# 4-Port_USB_HUB_SCH.net
KiCad netlist of a schematic drawn in Altium Designer
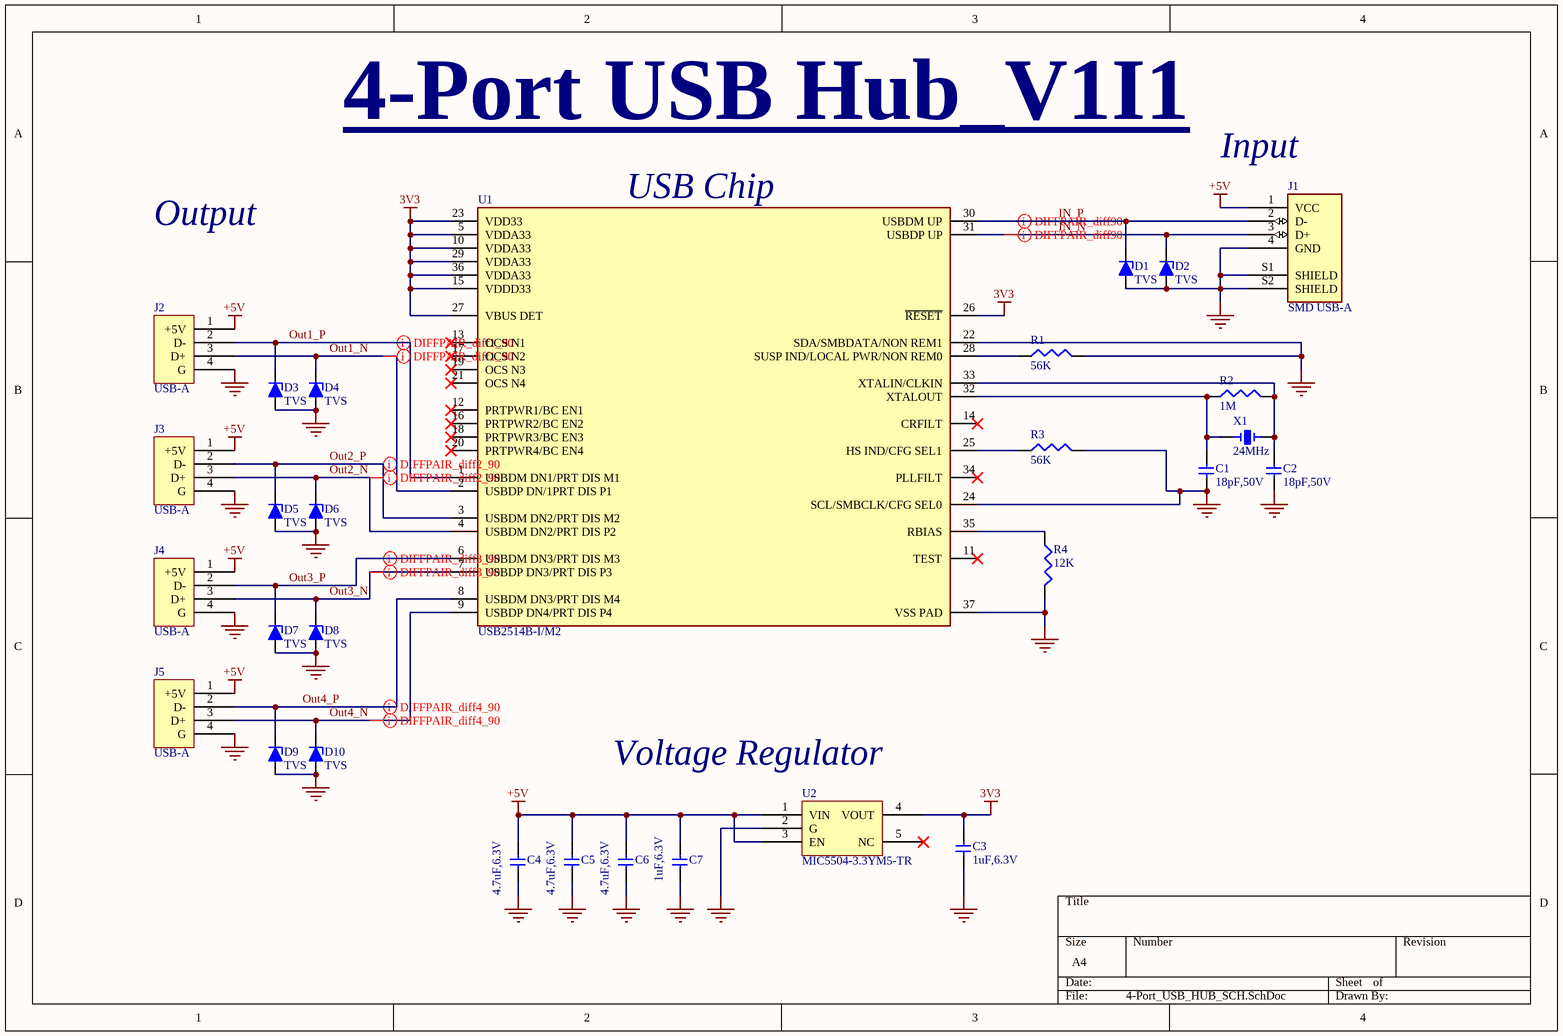
[diagram p0: 4-Port_USB_HUB_SCH.SchDoc]

(export (version "E")
  (design (tool "Eeschema 10.0.6"))
  (components
    (comp (ref "C1")
      (value "18pF,50V")
      (footprint "18pF")
      (description "18PF 50V 0805")
      (fields
        (field (name "MANUFACTURER") "KEMET")
        (field (name "MANUFACTURER PART NUMBER") "C0805C180J5GACTU")
      )
      (libsource (lib "4-Port_USB_HUB_SCHLib") (part "C0805C180J5GACTU"))
    )
    (comp (ref "C2")
      (value "18pF,50V")
      (footprint "18pF")
      (description "18PF 50V 0805")
      (fields
        (field (name "MANUFACTURER") "KEMET")
        (field (name "MANUFACTURER PART NUMBER") "C0805C180J5GACTU")
      )
      (libsource (lib "4-Port_USB_HUB_SCHLib") (part "C0805C180J5GACTU"))
    )
    (comp (ref "C3")
      (value "1uF,6.3V")
      (footprint "1uF_CAP")
      (description "1uF 6.3V 0402")
      (fields
        (field (name "MANUFACTURER") "KEMET")
        (field (name "MANUFACTURER PART NUMBER") "C0402C105K9PACTU")
      )
      (libsource (lib "4-Port_USB_HUB_SCHLib") (part "C0402C105K9PACTU"))
    )
    (comp (ref "C4")
      (value "4.7uF,6.3V")
      (footprint "4.7uF_CAP")
      (description "4.7uF 6.3V 0402")
      (fields
        (field (name "MANUFACTURER") "Murata")
        (field (name "MANUFACTURER PART NUMBER") "GRM155R60J475ME47D")
      )
      (libsource (lib "4-Port_USB_HUB_SCHLib") (part "GRM155R60J475ME47D"))
    )
    (comp (ref "C5")
      (value "4.7uF,6.3V")
      (footprint "4.7uF_CAP")
      (description "4.7uF 6.3V 0402")
      (fields
        (field (name "MANUFACTURER") "Murata")
        (field (name "MANUFACTURER PART NUMBER") "GRM155R60J475ME47D")
      )
      (libsource (lib "4-Port_USB_HUB_SCHLib") (part "GRM155R60J475ME47D"))
    )
    (comp (ref "C6")
      (value "4.7uF,6.3V")
      (footprint "4.7uF_CAP")
      (description "4.7uF 6.3V 0402")
      (fields
        (field (name "MANUFACTURER") "Murata")
        (field (name "MANUFACTURER PART NUMBER") "GRM155R60J475ME47D")
      )
      (libsource (lib "4-Port_USB_HUB_SCHLib") (part "GRM155R60J475ME47D"))
    )
    (comp (ref "C7")
      (value "1uF,6.3V")
      (footprint "1uF_CAP")
      (description "1uF 6.3V 0402")
      (fields
        (field (name "MANUFACTURER") "KEMET")
        (field (name "MANUFACTURER PART NUMBER") "C0402C105K9PACTU")
      )
      (libsource (lib "4-Port_USB_HUB_SCHLib") (part "C0402C105K9PACTU"))
    )
    (comp (ref "D1")
      (value "TVS")
      (footprint "ESD Diode")
      (description "TVS Diode")
      (fields
        (field (name "MANUFACTURER") "ON Semiconductor")
        (field (name "MANUFACTURER PART NUMBER") "ESD9B3.3ST5G")
      )
      (libsource (lib "4-Port_USB_HUB_SCHLib") (part "ESD9B3.3ST5G"))
    )
    (comp (ref "D2")
      (value "TVS")
      (footprint "ESD Diode")
      (description "TVS Diode")
      (fields
        (field (name "MANUFACTURER") "ON Semiconductor")
        (field (name "MANUFACTURER PART NUMBER") "ESD9B3.3ST5G")
      )
      (libsource (lib "4-Port_USB_HUB_SCHLib") (part "ESD9B3.3ST5G"))
    )
    (comp (ref "D3")
      (value "TVS")
      (footprint "ESD Diode")
      (description "TVS Diode")
      (fields
        (field (name "MANUFACTURER") "ON Semiconductor")
        (field (name "MANUFACTURER PART NUMBER") "ESD9B3.3ST5G")
      )
      (libsource (lib "4-Port_USB_HUB_SCHLib") (part "ESD9B3.3ST5G"))
    )
    (comp (ref "D4")
      (value "TVS")
      (footprint "ESD Diode")
      (description "TVS Diode")
      (fields
        (field (name "MANUFACTURER") "ON Semiconductor")
        (field (name "MANUFACTURER PART NUMBER") "ESD9B3.3ST5G")
      )
      (libsource (lib "4-Port_USB_HUB_SCHLib") (part "ESD9B3.3ST5G"))
    )
    (comp (ref "D5")
      (value "TVS")
      (footprint "ESD Diode")
      (description "TVS Diode")
      (fields
        (field (name "MANUFACTURER") "ON Semiconductor")
        (field (name "MANUFACTURER PART NUMBER") "ESD9B3.3ST5G")
      )
      (libsource (lib "4-Port_USB_HUB_SCHLib") (part "ESD9B3.3ST5G"))
    )
    (comp (ref "D6")
      (value "TVS")
      (footprint "ESD Diode")
      (description "TVS Diode")
      (fields
        (field (name "MANUFACTURER") "ON Semiconductor")
        (field (name "MANUFACTURER PART NUMBER") "ESD9B3.3ST5G")
      )
      (libsource (lib "4-Port_USB_HUB_SCHLib") (part "ESD9B3.3ST5G"))
    )
    (comp (ref "D7")
      (value "TVS")
      (footprint "ESD Diode")
      (description "TVS Diode")
      (fields
        (field (name "MANUFACTURER") "ON Semiconductor")
        (field (name "MANUFACTURER PART NUMBER") "ESD9B3.3ST5G")
      )
      (libsource (lib "4-Port_USB_HUB_SCHLib") (part "ESD9B3.3ST5G"))
    )
    (comp (ref "D8")
      (value "TVS")
      (footprint "ESD Diode")
      (description "TVS Diode")
      (fields
        (field (name "MANUFACTURER") "ON Semiconductor")
        (field (name "MANUFACTURER PART NUMBER") "ESD9B3.3ST5G")
      )
      (libsource (lib "4-Port_USB_HUB_SCHLib") (part "ESD9B3.3ST5G"))
    )
    (comp (ref "D9")
      (value "TVS")
      (footprint "ESD Diode")
      (description "TVS Diode")
      (fields
        (field (name "MANUFACTURER") "ON Semiconductor")
        (field (name "MANUFACTURER PART NUMBER") "ESD9B3.3ST5G")
      )
      (libsource (lib "4-Port_USB_HUB_SCHLib") (part "ESD9B3.3ST5G"))
    )
    (comp (ref "D10")
      (value "TVS")
      (footprint "ESD Diode")
      (description "TVS Diode")
      (fields
        (field (name "MANUFACTURER") "ON Semiconductor")
        (field (name "MANUFACTURER PART NUMBER") "ESD9B3.3ST5G")
      )
      (libsource (lib "4-Port_USB_HUB_SCHLib") (part "ESD9B3.3ST5G"))
    )
    (comp (ref "J1")
      (value "SMD USB-A")
      (footprint "SMD USB-A")
      (description "USB - A USB 2.0 Receptacle Connector 4 Position Surface Mount, Right Angle, Horizontal")
      (fields
        (field (name "MANUFACTURER") "Samtec")
        (field (name "MANUFACTURER PART NUMBER") "USB-A-S-S-B-SM2")
      )
      (libsource (lib "4-Port_USB_HUB_SCHLib") (part "USB-A-S-S-B-SM2"))
    )
    (comp (ref "J2")
      (value "USB-A")
      (footprint "USB_Connector")
      (description "Conn USB SKT 4 POS Solder ST Thru-Hole 4 Terminal 1 Port")
      (fields
        (field (name "MANUFACTURER") "Kycon")
        (field (name "MANUFACTURER PART NUMBER") "KUSBVX-AS1N-B30")
      )
      (libsource (lib "4-Port_USB_HUB_SCHLib") (part "KUSBVX-AS1N-B30"))
    )
    (comp (ref "J3")
      (value "USB-A")
      (footprint "USB_Connector")
      (description "Conn USB SKT 4 POS Solder ST Thru-Hole 4 Terminal 1 Port")
      (fields
        (field (name "MANUFACTURER") "Kycon")
        (field (name "MANUFACTURER PART NUMBER") "KUSBVX-AS1N-B30")
      )
      (libsource (lib "4-Port_USB_HUB_SCHLib") (part "KUSBVX-AS1N-B30"))
    )
    (comp (ref "J4")
      (value "USB-A")
      (footprint "USB_Connector")
      (description "Conn USB SKT 4 POS Solder ST Thru-Hole 4 Terminal 1 Port")
      (fields
        (field (name "MANUFACTURER") "Kycon")
        (field (name "MANUFACTURER PART NUMBER") "KUSBVX-AS1N-B30")
      )
      (libsource (lib "4-Port_USB_HUB_SCHLib") (part "KUSBVX-AS1N-B30"))
    )
    (comp (ref "J5")
      (value "USB-A")
      (footprint "USB_Connector")
      (description "Conn USB SKT 4 POS Solder ST Thru-Hole 4 Terminal 1 Port")
      (fields
        (field (name "MANUFACTURER") "Kycon")
        (field (name "MANUFACTURER PART NUMBER") "KUSBVX-AS1N-B30")
      )
      (libsource (lib "4-Port_USB_HUB_SCHLib") (part "KUSBVX-AS1N-B30"))
    )
    (comp (ref "R1")
      (value "56K")
      (footprint "56K")
      (fields
        (field (name "MANUFACTURER") "Yageo")
        (field (name "MANUFACTURER PART NUMBER") "RC0402JR-0756KL")
        (field (name "TOLERANCE") "5%")
      )
      (libsource (lib "4-Port_USB_HUB_SCHLib") (part "RC0402JR-0756KL"))
    )
    (comp (ref "R2")
      (value "1M")
      (footprint "1M Res")
      (description "1M OHM")
      (fields
        (field (name "MANUFACTURER") "Yageo")
        (field (name "MANUFACTURER PART NUMBER") "RC0402FR-071ML")
      )
      (libsource (lib "4-Port_USB_HUB_SCHLib") (part "RC0402FR-071ML"))
    )
    (comp (ref "R3")
      (value "56K")
      (footprint "56K")
      (fields
        (field (name "MANUFACTURER") "Yageo")
        (field (name "MANUFACTURER PART NUMBER") "RC0402JR-0756KL")
        (field (name "TOLERANCE") "5%")
      )
      (libsource (lib "4-Port_USB_HUB_SCHLib") (part "RC0402JR-0756KL"))
    )
    (comp (ref "R4")
      (value "12K")
      (footprint "1M Res")
      (description "12K OHM")
      (fields
        (field (name "MANUFACTURER") "Yageo")
        (field (name "MANUFACTURER PART NUMBER") "RC0402JR-0712KL")
      )
      (libsource (lib "4-Port_USB_HUB_SCHLib") (part "RC0402JR-0712KL"))
    )
    (comp (ref "U1")
      (value "USB2514B-I/M2")
      (footprint "IC_microchip")
      (description "USB2514B-I/M2, USB Interface, USB Hub Controller, USB 2.0, 3 V, 3.6 V, SQFN, 36 Pins")
      (fields (field (name "MANUFACTURER") "Microchip"))
      (libsource (lib "4-Port_USB_HUB_SCHLib") (part "USB2514B-I/M2"))
    )
    (comp (ref "U2")
      (value "MIC5504-3.3YM5-TR")
      (footprint "Voltage Regulator")
      (description "MIC5504-3.3YM5-TR - LDO VOLT REG, 0.3A, 3.3V, SOT-23-5")
      (fields (field (name "MANUFACTURER") "Microchip"))
      (libsource (lib "4-Port_USB_HUB_SCHLib") (part "MIC5504-3.3YM5-TR"))
    )
    (comp (ref "X1")
      (value "24MHz")
      (footprint "Crystal")
      (description "24MHZ")
      (fields
        (field (name "MANUFACTURER") "Murata")
        (field (name "MANUFACTURER PART NUMBER") "XRCGB24M000F0L00R0")
      )
      (libsource (lib "4-Port_USB_HUB_SCHLib") (part "XRCGB24M000F0L00R0"))
    )
  )
  (nets
    (net (code "1") (name "+5V") (class "Default")
      (node (ref "C4") (pin "1") (pinfunction "1_1") (pintype "passive"))
      (node (ref "C5") (pin "1") (pinfunction "1_1") (pintype "passive"))
      (node (ref "C6") (pin "1") (pinfunction "1_1") (pintype "passive"))
      (node (ref "C7") (pin "1") (pinfunction "1_1") (pintype "passive"))
      (node (ref "J1") (pin "1") (pinfunction "VCC_1") (pintype "power_in"))
      (node (ref "J2") (pin "1") (pinfunction "+5V_1") (pintype "passive"))
      (node (ref "J3") (pin "1") (pinfunction "+5V_1") (pintype "passive"))
      (node (ref "J4") (pin "1") (pinfunction "+5V_1") (pintype "passive"))
      (node (ref "J5") (pin "1") (pinfunction "+5V_1") (pintype "passive"))
      (node (ref "U2") (pin "1") (pinfunction "VIN_1") (pintype "passive"))
      (node (ref "U2") (pin "3") (pinfunction "EN_3") (pintype "passive"))
    )
    (net (code "2") (name "/IN_N") (class "Default")
      (node (ref "D2") (pin "2") (pinfunction "2_2") (pintype "passive"))
      (node (ref "J1") (pin "3") (pinfunction "D+_3") (pintype "bidirectional"))
      (node (ref "U1") (pin "31") (pinfunction "USBDP_UP_31") (pintype "passive"))
    )
    (net (code "3") (name "/IN_P") (class "Default")
      (node (ref "D1") (pin "2") (pinfunction "2_2") (pintype "passive"))
      (node (ref "J1") (pin "2") (pinfunction "D-_2") (pintype "bidirectional"))
      (node (ref "U1") (pin "30") (pinfunction "USBDM_UP_30") (pintype "passive"))
    )
    (net (code "4") (name "/Out1_N") (class "Default")
      (node (ref "D4") (pin "2") (pinfunction "2_2") (pintype "passive"))
      (node (ref "J2") (pin "3") (pinfunction "D+_3") (pintype "passive"))
      (node (ref "U1") (pin "2") (pinfunction "USBDP_DN/1PRT_DIS_P1_2") (pintype "passive"))
    )
    (net (code "5") (name "/Out1_P") (class "Default")
      (node (ref "D3") (pin "2") (pinfunction "2_2") (pintype "passive"))
      (node (ref "J2") (pin "2") (pinfunction "D-_2") (pintype "passive"))
      (node (ref "U1") (pin "1") (pinfunction "USBDM_DN1/PRT_DIS_M1_1") (pintype "passive"))
    )
    (net (code "6") (name "/Out2_N") (class "Default")
      (node (ref "D6") (pin "2") (pinfunction "2_2") (pintype "passive"))
      (node (ref "J3") (pin "3") (pinfunction "D+_3") (pintype "passive"))
      (node (ref "U1") (pin "4") (pinfunction "USBDM_DN2/PRT_DIS_P2_4") (pintype "passive"))
    )
    (net (code "7") (name "/Out2_P") (class "Default")
      (node (ref "D5") (pin "2") (pinfunction "2_2") (pintype "passive"))
      (node (ref "J3") (pin "2") (pinfunction "D-_2") (pintype "passive"))
      (node (ref "U1") (pin "3") (pinfunction "USBDM_DN2/PRT_DIS_M2_3") (pintype "passive"))
    )
    (net (code "8") (name "/Out3_N") (class "Default")
      (node (ref "D8") (pin "2") (pinfunction "2_2") (pintype "passive"))
      (node (ref "J4") (pin "3") (pinfunction "D+_3") (pintype "passive"))
      (node (ref "U1") (pin "7") (pinfunction "USBDP_DN3/PRT_DIS_P3_7") (pintype "passive"))
    )
    (net (code "9") (name "/Out3_P") (class "Default")
      (node (ref "D7") (pin "2") (pinfunction "2_2") (pintype "passive"))
      (node (ref "J4") (pin "2") (pinfunction "D-_2") (pintype "passive"))
      (node (ref "U1") (pin "6") (pinfunction "USBDM_DN3/PRT_DIS_M3_6") (pintype "passive"))
    )
    (net (code "10") (name "/Out4_N") (class "Default")
      (node (ref "D10") (pin "2") (pinfunction "2_2") (pintype "passive"))
      (node (ref "J5") (pin "3") (pinfunction "D+_3") (pintype "passive"))
      (node (ref "U1") (pin "9") (pinfunction "USBDP_DN4/PRT_DIS_P4_9") (pintype "passive"))
    )
    (net (code "11") (name "/Out4_P") (class "Default")
      (node (ref "D9") (pin "2") (pinfunction "2_2") (pintype "passive"))
      (node (ref "J5") (pin "2") (pinfunction "D-_2") (pintype "passive"))
      (node (ref "U1") (pin "8") (pinfunction "USBDM_DN3/PRT_DIS_M4_8") (pintype "passive"))
    )
    (net (code "12") (name "3V3") (class "Default")
      (node (ref "C3") (pin "1") (pinfunction "1_1") (pintype "passive"))
      (node (ref "U1") (pin "10") (pinfunction "VDDA33_10") (pintype "passive"))
      (node (ref "U1") (pin "15") (pinfunction "VDDD33_15") (pintype "passive"))
      (node (ref "U1") (pin "23") (pinfunction "VDD33_23") (pintype "passive"))
      (node (ref "U1") (pin "26") (pinfunction "~{RESET}_26") (pintype "passive"))
      (node (ref "U1") (pin "27") (pinfunction "VBUS_DET_27") (pintype "passive"))
      (node (ref "U1") (pin "29") (pinfunction "VDDA33_29") (pintype "passive"))
      (node (ref "U1") (pin "36") (pinfunction "VDDA33_36") (pintype "passive"))
      (node (ref "U1") (pin "5") (pinfunction "VDDA33_5") (pintype "passive"))
      (node (ref "U2") (pin "4") (pinfunction "VOUT_4") (pintype "passive"))
    )
    (net (code "13") (name "GND") (class "Default")
      (node (ref "C1") (pin "2") (pinfunction "2_2") (pintype "passive"))
      (node (ref "C2") (pin "2") (pinfunction "2_2") (pintype "passive"))
      (node (ref "C3") (pin "2") (pinfunction "2_2") (pintype "passive"))
      (node (ref "C4") (pin "2") (pinfunction "2_2") (pintype "passive"))
      (node (ref "C5") (pin "2") (pinfunction "2_2") (pintype "passive"))
      (node (ref "C6") (pin "2") (pinfunction "2_2") (pintype "passive"))
      (node (ref "C7") (pin "2") (pinfunction "2_2") (pintype "passive"))
      (node (ref "D1") (pin "1") (pinfunction "1_1") (pintype "passive"))
      (node (ref "D10") (pin "1") (pinfunction "1_1") (pintype "passive"))
      (node (ref "D2") (pin "1") (pinfunction "1_1") (pintype "passive"))
      (node (ref "D3") (pin "1") (pinfunction "1_1") (pintype "passive"))
      (node (ref "D4") (pin "1") (pinfunction "1_1") (pintype "passive"))
      (node (ref "D5") (pin "1") (pinfunction "1_1") (pintype "passive"))
      (node (ref "D6") (pin "1") (pinfunction "1_1") (pintype "passive"))
      (node (ref "D7") (pin "1") (pinfunction "1_1") (pintype "passive"))
      (node (ref "D8") (pin "1") (pinfunction "1_1") (pintype "passive"))
      (node (ref "D9") (pin "1") (pinfunction "1_1") (pintype "passive"))
      (node (ref "J1") (pin "4") (pinfunction "GND_4") (pintype "power_in"))
      (node (ref "J1") (pin "S1") (pinfunction "SHIELD_S1") (pintype "passive"))
      (node (ref "J1") (pin "S2") (pinfunction "SHIELD_S2") (pintype "passive"))
      (node (ref "J2") (pin "4") (pinfunction "G_4") (pintype "passive"))
      (node (ref "J3") (pin "4") (pinfunction "G_4") (pintype "passive"))
      (node (ref "J4") (pin "4") (pinfunction "G_4") (pintype "passive"))
      (node (ref "J5") (pin "4") (pinfunction "G_4") (pintype "passive"))
      (node (ref "R1") (pin "2") (pinfunction "2_2") (pintype "passive"))
      (node (ref "R3") (pin "2") (pinfunction "2_2") (pintype "passive"))
      (node (ref "R4") (pin "2") (pinfunction "2_2") (pintype "passive"))
      (node (ref "U1") (pin "22") (pinfunction "SDA/SMBDATA/NON_REM1_22") (pintype "passive"))
      (node (ref "U1") (pin "24") (pinfunction "SCL/SMBCLK/CFG_SEL0_24") (pintype "passive"))
      (node (ref "U1") (pin "37") (pinfunction "VSS_PAD_37") (pintype "passive"))
      (node (ref "U2") (pin "2") (pinfunction "G_2") (pintype "passive"))
    )
    (net (code "14") (name "Net-(U1-HS_IND{slash}CFG_SEL1)") (class "Default")
      (node (ref "R3") (pin "1") (pinfunction "1_1") (pintype "passive"))
      (node (ref "U1") (pin "25") (pinfunction "HS_IND/CFG_SEL1_25") (pintype "passive"))
    )
    (net (code "15") (name "Net-(U1-RBIAS)") (class "Default")
      (node (ref "R4") (pin "1") (pinfunction "1_1") (pintype "passive"))
      (node (ref "U1") (pin "35") (pinfunction "RBIAS_35") (pintype "passive"))
    )
    (net (code "16") (name "Net-(U1-SUSP_IND{slash}LOCAL_PWR{slash}NON_REM0)") (class "Default")
      (node (ref "R1") (pin "1") (pinfunction "1_1") (pintype "passive"))
      (node (ref "U1") (pin "28") (pinfunction "SUSP_IND/LOCAL_PWR/NON_REM0_28") (pintype "passive"))
    )
    (net (code "17") (name "Net-(U1-XTALIN{slash}CLKIN)") (class "Default")
      (node (ref "C2") (pin "1") (pinfunction "1_1") (pintype "passive"))
      (node (ref "R2") (pin "2") (pinfunction "2_2") (pintype "passive"))
      (node (ref "U1") (pin "33") (pinfunction "XTALIN/CLKIN_33") (pintype "passive"))
      (node (ref "X1") (pin "3") (pinfunction "3_3") (pintype "passive"))
    )
    (net (code "18") (name "Net-(U1-XTALOUT)") (class "Default")
      (node (ref "C1") (pin "1") (pinfunction "1_1") (pintype "passive"))
      (node (ref "R2") (pin "1") (pinfunction "1_1") (pintype "passive"))
      (node (ref "U1") (pin "32") (pinfunction "XTALOUT_32") (pintype "passive"))
      (node (ref "X1") (pin "1") (pinfunction "1_1") (pintype "passive"))
    )
    (net (code "19") (name "unconnected-(U1-CRFILT-Pad14)") (class "Default")
      (node (ref "U1") (pin "14") (pinfunction "CRFILT_14") (pintype "passive+no_connect"))
    )
    (net (code "20") (name "unconnected-(U1-OCS_N1-Pad13)") (class "Default")
      (node (ref "U1") (pin "13") (pinfunction "OCS_N1_13") (pintype "passive+no_connect"))
    )
    (net (code "21") (name "unconnected-(U1-OCS_N2-Pad17)") (class "Default")
      (node (ref "U1") (pin "17") (pinfunction "OCS_N2_17") (pintype "passive+no_connect"))
    )
    (net (code "22") (name "unconnected-(U1-OCS_N3-Pad19)") (class "Default")
      (node (ref "U1") (pin "19") (pinfunction "OCS_N3_19") (pintype "passive+no_connect"))
    )
    (net (code "23") (name "unconnected-(U1-OCS_N4-Pad21)") (class "Default")
      (node (ref "U1") (pin "21") (pinfunction "OCS_N4_21") (pintype "passive+no_connect"))
    )
    (net (code "24") (name "unconnected-(U1-PLLFILT-Pad34)") (class "Default")
      (node (ref "U1") (pin "34") (pinfunction "PLLFILT_34") (pintype "passive+no_connect"))
    )
    (net (code "25") (name "unconnected-(U1-PRTPWR1{slash}BC_EN1-Pad12)") (class "Default")
      (node (ref "U1") (pin "12") (pinfunction "PRTPWR1/BC_EN1_12") (pintype "passive+no_connect"))
    )
    (net (code "26") (name "unconnected-(U1-PRTPWR2{slash}BC_EN2-Pad16)") (class "Default")
      (node (ref "U1") (pin "16") (pinfunction "PRTPWR2/BC_EN2_16") (pintype "passive+no_connect"))
    )
    (net (code "27") (name "unconnected-(U1-PRTPWR3{slash}BC_EN3-Pad18)") (class "Default")
      (node (ref "U1") (pin "18") (pinfunction "PRTPWR3/BC_EN3_18") (pintype "passive+no_connect"))
    )
    (net (code "28") (name "unconnected-(U1-PRTPWR4{slash}BC_EN4-Pad20)") (class "Default")
      (node (ref "U1") (pin "20") (pinfunction "PRTPWR4/BC_EN4_20") (pintype "passive+no_connect"))
    )
    (net (code "29") (name "unconnected-(U1-TEST-Pad11)") (class "Default")
      (node (ref "U1") (pin "11") (pinfunction "TEST_11") (pintype "passive+no_connect"))
    )
    (net (code "30") (name "unconnected-(U2-NC-Pad5)") (class "Default")
      (node (ref "U2") (pin "5") (pinfunction "NC_5") (pintype "passive+no_connect"))
    )
  )
)
